# a1200-led.net
KiCad netlist of a schematic drawn in EAGLE
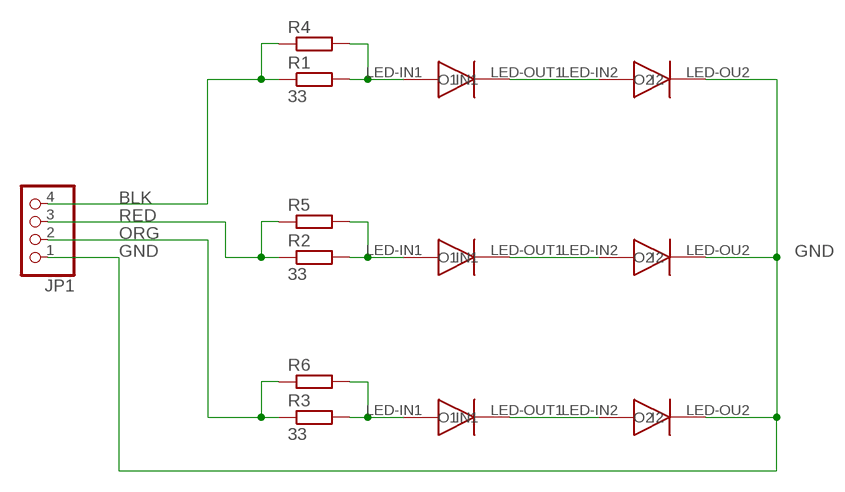
[diagram p0: schematic, sheet 1]

(export (version "E")
  (design (tool "Eeschema 10.0.6"))
  (components
    (comp (ref "JP1")
      (value "PINHD-1X4")
      (footprint "eagle-import:1X04")
      (libsource (lib "eagle-import") (part "PINHD-1X4"))
    )
    (comp (ref "LED1")
      (value "A1200-LED")
      (footprint "eagle-import:A1200-LED")
      (libsource (lib "eagle-import") (part "A1200-LED"))
    )
    (comp (ref "LED2")
      (value "A1200-LED")
      (footprint "eagle-import:A1200-LED")
      (libsource (lib "eagle-import") (part "A1200-LED"))
    )
    (comp (ref "LED3")
      (value "A1200-LED")
      (footprint "eagle-import:A1200-LED")
      (libsource (lib "eagle-import") (part "A1200-LED"))
    )
    (comp (ref "R1")
      (value "33")
      (footprint "eagle-import:0207_10")
      (libsource (lib "eagle-import") (part "R-EU_0207/10"))
    )
    (comp (ref "R2")
      (value "33")
      (footprint "eagle-import:0207_10")
      (libsource (lib "eagle-import") (part "R-EU_0207/10"))
    )
    (comp (ref "R3")
      (value "33")
      (footprint "eagle-import:0207_10")
      (libsource (lib "eagle-import") (part "R-EU_0207/10"))
    )
    (comp (ref "R4")
      (value "R-EU_R1206")
      (footprint "eagle-import:R1206")
      (libsource (lib "eagle-import") (part "R-EU_R1206"))
    )
    (comp (ref "R5")
      (value "R-EU_R1206")
      (footprint "eagle-import:R1206")
      (libsource (lib "eagle-import") (part "R-EU_R1206"))
    )
    (comp (ref "R6")
      (value "R-EU_R1206")
      (footprint "eagle-import:R1206")
      (libsource (lib "eagle-import") (part "R-EU_R1206"))
    )
  )
  (nets
    (net (code "1") (name "/BLK") (class "Default")
      (node (ref "JP1") (pin "4") (pinfunction "4_4") (pintype "passive"))
      (node (ref "R1") (pin "1") (pinfunction "1_1") (pintype "passive"))
      (node (ref "R4") (pin "1") (pinfunction "1_1") (pintype "passive"))
    )
    (net (code "2") (name "/GND") (class "Default")
      (node (ref "JP1") (pin "1") (pinfunction "1_1") (pintype "passive"))
      (node (ref "LED1") (pin "LED-OU2") (pinfunction "O2_LED-OU2") (pintype "bidirectional"))
      (node (ref "LED2") (pin "LED-OU2") (pinfunction "O2_LED-OU2") (pintype "bidirectional"))
      (node (ref "LED3") (pin "LED-OU2") (pinfunction "O2_LED-OU2") (pintype "bidirectional"))
    )
    (net (code "3") (name "/ORG") (class "Default")
      (node (ref "JP1") (pin "2") (pinfunction "2_2") (pintype "passive"))
      (node (ref "R3") (pin "1") (pinfunction "1_1") (pintype "passive"))
      (node (ref "R6") (pin "1") (pinfunction "1_1") (pintype "passive"))
    )
    (net (code "4") (name "/RED") (class "Default")
      (node (ref "JP1") (pin "3") (pinfunction "3_3") (pintype "passive"))
      (node (ref "R2") (pin "1") (pinfunction "1_1") (pintype "passive"))
      (node (ref "R5") (pin "1") (pinfunction "1_1") (pintype "passive"))
    )
    (net (code "5") (name "Net-(LED1-I2)") (class "Default")
      (node (ref "LED1") (pin "LED-IN2") (pinfunction "I2_LED-IN2") (pintype "bidirectional"))
      (node (ref "LED1") (pin "LED-OUT1") (pinfunction "O1_LED-OUT1") (pintype "bidirectional"))
    )
    (net (code "6") (name "Net-(LED1-IN1)") (class "Default")
      (node (ref "LED1") (pin "LED-IN1") (pinfunction "IN1_LED-IN1") (pintype "bidirectional"))
      (node (ref "R1") (pin "2") (pinfunction "2_2") (pintype "passive"))
      (node (ref "R4") (pin "2") (pinfunction "2_2") (pintype "passive"))
    )
    (net (code "7") (name "Net-(LED2-I2)") (class "Default")
      (node (ref "LED2") (pin "LED-IN2") (pinfunction "I2_LED-IN2") (pintype "bidirectional"))
      (node (ref "LED2") (pin "LED-OUT1") (pinfunction "O1_LED-OUT1") (pintype "bidirectional"))
    )
    (net (code "8") (name "Net-(LED2-IN1)") (class "Default")
      (node (ref "LED2") (pin "LED-IN1") (pinfunction "IN1_LED-IN1") (pintype "bidirectional"))
      (node (ref "R2") (pin "2") (pinfunction "2_2") (pintype "passive"))
      (node (ref "R5") (pin "2") (pinfunction "2_2") (pintype "passive"))
    )
    (net (code "9") (name "Net-(LED3-I2)") (class "Default")
      (node (ref "LED3") (pin "LED-IN2") (pinfunction "I2_LED-IN2") (pintype "bidirectional"))
      (node (ref "LED3") (pin "LED-OUT1") (pinfunction "O1_LED-OUT1") (pintype "bidirectional"))
    )
    (net (code "10") (name "Net-(LED3-IN1)") (class "Default")
      (node (ref "LED3") (pin "LED-IN1") (pinfunction "IN1_LED-IN1") (pintype "bidirectional"))
      (node (ref "R3") (pin "2") (pinfunction "2_2") (pintype "passive"))
      (node (ref "R6") (pin "2") (pinfunction "2_2") (pintype "passive"))
    )
  )
)
